# EasyEDAProProject.net
KiCad netlist of a schematic drawn in EasyEDA Pro
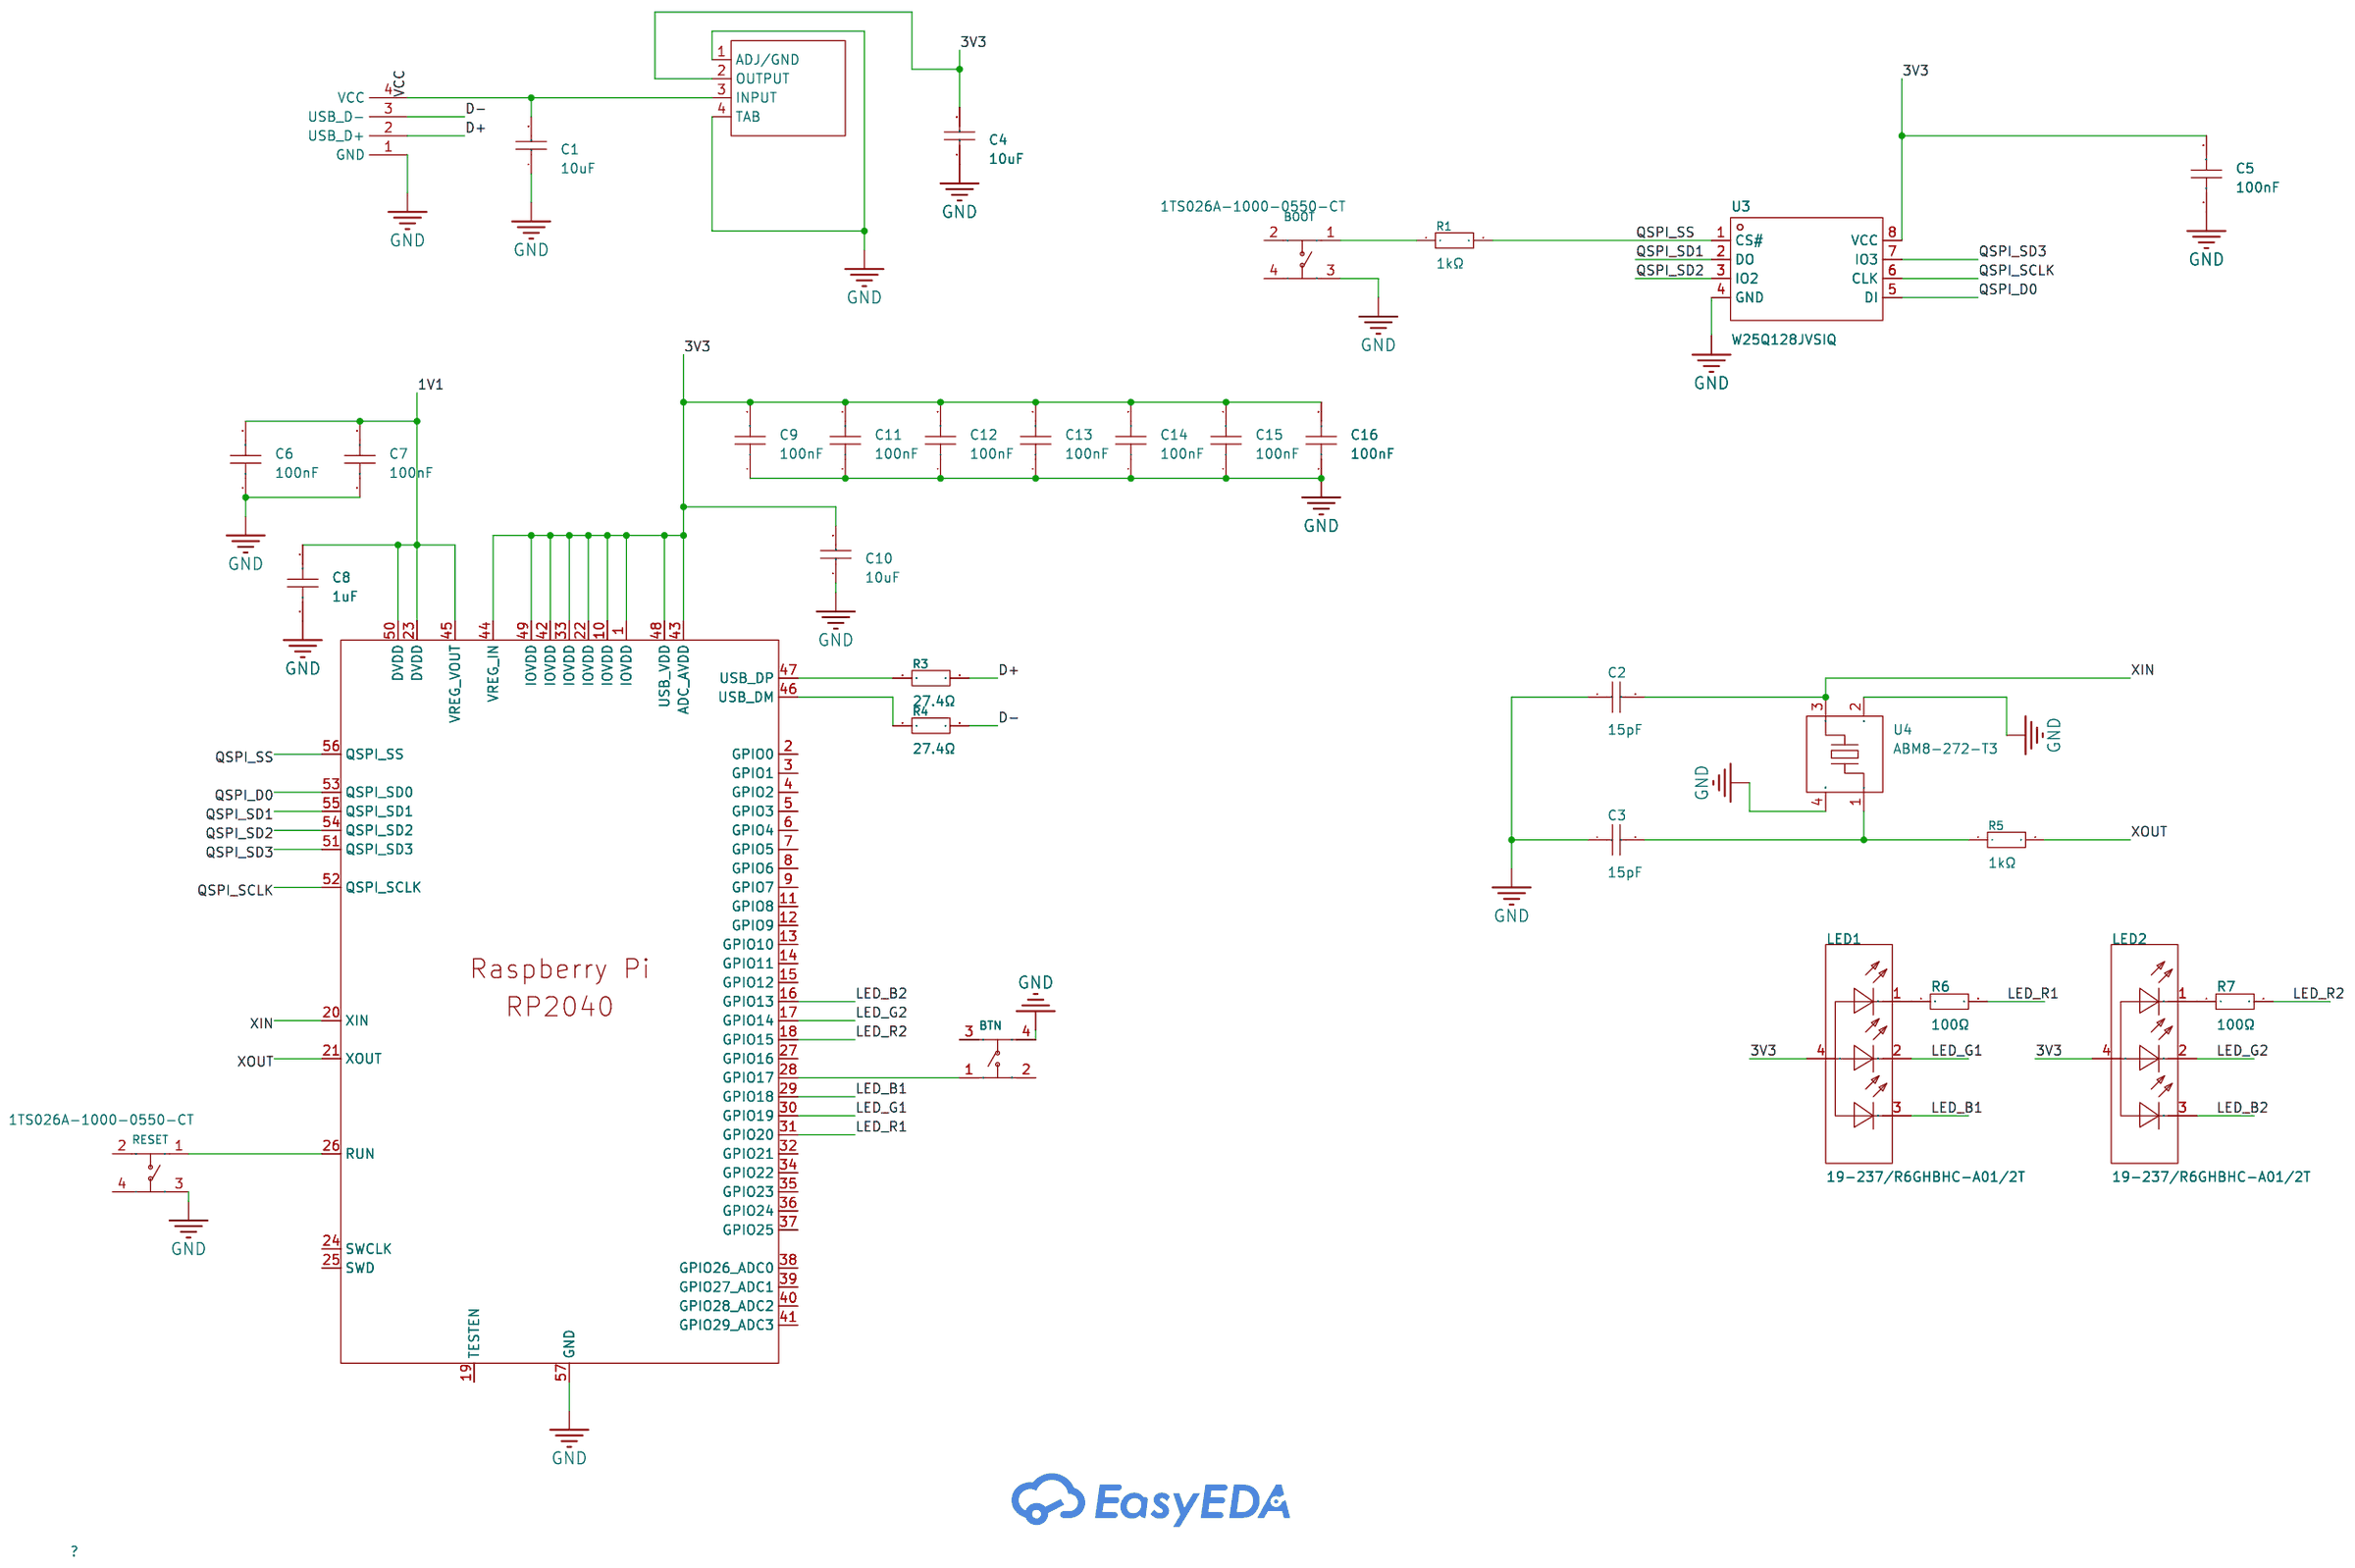
[diagram p0: schematic sheet]

(export (version "E")
  (design (tool "Eeschema 10.0.6"))
  (components
    (comp (ref "BOOT")
      (value "1TS026A-1000-0550-CT")
      (footprint "easyedapro:SW-SMD_4P-L2.6-W1.6-P0.75-LS3.0")
      (fields (field (name "Manufacturer") "HYP(鸿源精密)"))
      (libsource (lib "easyedapro") (part "1TS026A-1000-0550-CT"))
    )
    (comp (ref "BTN")
      (value "1TS026A-1000-0550-CT")
      (footprint "easyedapro:SW-SMD_4P-L2.6-W1.6-P0.75-LS3.0")
      (fields (field (name "Manufacturer") "HYP(鸿源精密)"))
      (libsource (lib "easyedapro") (part "1TS026A-1000-0550-CT"))
    )
    (comp (ref "C1")
      (value "10uF")
      (footprint "easyedapro:C0402")
      (fields
        (field (name "Manufacturer Part") "CL05A106MQ5NUNC")
        (field (name "Manufacturer") "SAMSUNG(三星)")
      )
      (libsource (lib "easyedapro") (part "CL05A106MQ5NUNC"))
    )
    (comp (ref "C2")
      (value "15pF")
      (footprint "easyedapro:C0402")
      (fields (field (name "Manufacturer Part") "0402CG150J500NT") (field (name "Manufacturer") "FH(风华)"))
      (libsource (lib "easyedapro") (part "0402CG150J500NT"))
    )
    (comp (ref "C3")
      (value "15pF")
      (footprint "easyedapro:C0402")
      (fields (field (name "Manufacturer Part") "0402CG150J500NT") (field (name "Manufacturer") "FH(风华)"))
      (libsource (lib "easyedapro") (part "0402CG150J500NT"))
    )
    (comp (ref "C4")
      (value "10uF")
      (footprint "easyedapro:C0402")
      (fields
        (field (name "Manufacturer Part") "CL05A106MQ5NUNC")
        (field (name "Manufacturer") "SAMSUNG(三星)")
      )
      (libsource (lib "easyedapro") (part "CL05A106MQ5NUNC"))
    )
    (comp (ref "C5")
      (value "100nF")
      (footprint "easyedapro:C0402")
      (fields
        (field (name "Manufacturer Part") "CL05B104KO5NNNC")
        (field (name "Manufacturer") "SAMSUNG(三星)")
      )
      (libsource (lib "easyedapro") (part "CL05B104KO5NNNC"))
    )
    (comp (ref "C6")
      (value "100nF")
      (footprint "easyedapro:C0402")
      (fields
        (field (name "Manufacturer Part") "CL05B104KO5NNNC")
        (field (name "Manufacturer") "SAMSUNG(三星)")
      )
      (libsource (lib "easyedapro") (part "CL05B104KO5NNNC"))
    )
    (comp (ref "C7")
      (value "100nF")
      (footprint "easyedapro:C0402")
      (fields
        (field (name "Manufacturer Part") "CL05B104KO5NNNC")
        (field (name "Manufacturer") "SAMSUNG(三星)")
      )
      (libsource (lib "easyedapro") (part "CL05B104KO5NNNC"))
    )
    (comp (ref "C8")
      (value "1uF")
      (footprint "easyedapro:C0402")
      (fields
        (field (name "Manufacturer Part") "CL05A105KA5NQNC")
        (field (name "Manufacturer") "SAMSUNG(三星)")
      )
      (libsource (lib "easyedapro") (part "CL05A105KA5NQNC"))
    )
    (comp (ref "C9")
      (value "100nF")
      (footprint "easyedapro:C0402")
      (fields
        (field (name "Manufacturer Part") "CL05B104KO5NNNC")
        (field (name "Manufacturer") "SAMSUNG(三星)")
      )
      (libsource (lib "easyedapro") (part "CL05B104KO5NNNC"))
    )
    (comp (ref "C10")
      (value "10uF")
      (footprint "easyedapro:C0402")
      (fields
        (field (name "Manufacturer Part") "CL05A106MQ5NUNC")
        (field (name "Manufacturer") "SAMSUNG(三星)")
      )
      (libsource (lib "easyedapro") (part "CL05A106MQ5NUNC"))
    )
    (comp (ref "C11")
      (value "100nF")
      (footprint "easyedapro:C0402")
      (fields
        (field (name "Manufacturer Part") "CL05B104KO5NNNC")
        (field (name "Manufacturer") "SAMSUNG(三星)")
      )
      (libsource (lib "easyedapro") (part "CL05B104KO5NNNC"))
    )
    (comp (ref "C12")
      (value "100nF")
      (footprint "easyedapro:C0402")
      (fields
        (field (name "Manufacturer Part") "CL05B104KO5NNNC")
        (field (name "Manufacturer") "SAMSUNG(三星)")
      )
      (libsource (lib "easyedapro") (part "CL05B104KO5NNNC"))
    )
    (comp (ref "C13")
      (value "100nF")
      (footprint "easyedapro:C0402")
      (fields
        (field (name "Manufacturer Part") "CL05B104KO5NNNC")
        (field (name "Manufacturer") "SAMSUNG(三星)")
      )
      (libsource (lib "easyedapro") (part "CL05B104KO5NNNC"))
    )
    (comp (ref "C14")
      (value "100nF")
      (footprint "easyedapro:C0402")
      (fields
        (field (name "Manufacturer Part") "CL05B104KO5NNNC")
        (field (name "Manufacturer") "SAMSUNG(三星)")
      )
      (libsource (lib "easyedapro") (part "CL05B104KO5NNNC"))
    )
    (comp (ref "C15")
      (value "100nF")
      (footprint "easyedapro:C0402")
      (fields
        (field (name "Manufacturer Part") "CL05B104KO5NNNC")
        (field (name "Manufacturer") "SAMSUNG(三星)")
      )
      (libsource (lib "easyedapro") (part "CL05B104KO5NNNC"))
    )
    (comp (ref "C16")
      (value "100nF")
      (footprint "easyedapro:C0402")
      (fields
        (field (name "Manufacturer Part") "CL05B104KO5NNNC")
        (field (name "Manufacturer") "SAMSUNG(三星)")
      )
      (libsource (lib "easyedapro") (part "CL05B104KO5NNNC"))
    )
    (comp (ref "LED1")
      (value "19-237/R6GHBHC-A01/2T")
      (footprint "easyedapro:LED-ARRAY-SMD_4P-L1.6-W1.6-BL-CW")
      (fields (field (name "Manufacturer") "EVERLIGHT(亿光)"))
      (libsource (lib "easyedapro") (part "19-237/R6GHBHC-A01/2T"))
    )
    (comp (ref "LED2")
      (value "19-237/R6GHBHC-A01/2T")
      (footprint "easyedapro:LED-ARRAY-SMD_4P-L1.6-W1.6-BL-CW")
      (fields (field (name "Manufacturer") "EVERLIGHT(亿光)"))
      (libsource (lib "easyedapro") (part "19-237/R6GHBHC-A01/2T"))
    )
    (comp (ref "R1")
      (value "1kΩ")
      (footprint "easyedapro:R0402")
      (fields
        (field (name "Manufacturer Part") "0402WGF1001TCE")
        (field (name "Manufacturer") "UNI-ROYAL(厚声)")
      )
      (libsource (lib "easyedapro") (part "0402WGF1001TCE"))
    )
    (comp (ref "R3")
      (value "27.4Ω")
      (footprint "easyedapro:R0402")
      (fields
        (field (name "Manufacturer Part") "0402WGF274JTCE")
        (field (name "Manufacturer") "UNI-ROYAL(厚声)")
      )
      (libsource (lib "easyedapro") (part "0402WGF274JTCE"))
    )
    (comp (ref "R4")
      (value "27.4Ω")
      (footprint "easyedapro:R0402")
      (fields
        (field (name "Manufacturer Part") "0402WGF274JTCE")
        (field (name "Manufacturer") "UNI-ROYAL(厚声)")
      )
      (libsource (lib "easyedapro") (part "0402WGF274JTCE"))
    )
    (comp (ref "R5")
      (value "1kΩ")
      (footprint "easyedapro:R0402")
      (fields
        (field (name "Manufacturer Part") "0402WGF1001TCE")
        (field (name "Manufacturer") "UNI-ROYAL(厚声)")
      )
      (libsource (lib "easyedapro") (part "0402WGF1001TCE"))
    )
    (comp (ref "R6")
      (value "100Ω")
      (footprint "easyedapro:R0402")
      (fields
        (field (name "Manufacturer Part") "0402WGF1000TCE")
        (field (name "Manufacturer") "UNI-ROYAL(厚声)")
      )
      (libsource (lib "easyedapro") (part "0402WGF1000TCE"))
    )
    (comp (ref "R7")
      (value "100Ω")
      (footprint "easyedapro:R0402")
      (fields
        (field (name "Manufacturer Part") "0402WGF1000TCE")
        (field (name "Manufacturer") "UNI-ROYAL(厚声)")
      )
      (libsource (lib "easyedapro") (part "0402WGF1000TCE"))
    )
    (comp (ref "RESET")
      (value "1TS026A-1000-0550-CT")
      (footprint "easyedapro:SW-SMD_4P-L2.6-W1.6-P0.75-LS3.0")
      (fields (field (name "Manufacturer") "HYP(鸿源精密)"))
      (libsource (lib "easyedapro") (part "1TS026A-1000-0550-CT"))
    )
    (comp (ref "U1")
      (value "RP2040")
      (footprint "easyedapro:QFN-56_L7.0-W7.0-P0.40-TL-EP4.0")
      (fields (field (name "Manufacturer") "Raspberry Pi(树莓派)"))
      (libsource (lib "easyedapro") (part "RP2040_C2961140"))
    )
    (comp (ref "U2")
      (value "NCP1117ST33T3G")
      (footprint "easyedapro:SOT-223-3_L6.5-W3.4-P2.30-LS7.0-BR")
      (fields (field (name "Manufacturer") "onsemi(安森美)"))
      (libsource (lib "easyedapro") (part "NCP1117ST33T3G"))
    )
    (comp (ref "U3")
      (value "W25Q128JVSIQ")
      (footprint "easyedapro:SOIC-8_L5.3-W5.3-P1.27-LS8.0-BL")
      (fields (field (name "Manufacturer") "WINBOND(华邦)"))
      (libsource (lib "easyedapro") (part "W25Q128JVSIQTR"))
    )
    (comp (ref "U4")
      (value "ABM8-272-T3")
      (footprint "easyedapro:CRYSTAL-SMD_4P-L3.2-W2.5-BL")
      (fields (field (name "Manufacturer") "ABRACON"))
      (libsource (lib "easyedapro") (part "ABM8-272-T3_C20625731"))
    )
    (comp (ref "X1")
      (value "~")
      (footprint "easyedapro:USBA_PCB")
      (description "USB-A PCB")
      (libsource (lib "easyedapro") (part "USBA_PCB"))
    )
  )
  (nets
    (net (code "1") (name "/1V1") (class "Default")
      (node (ref "C6") (pin "2") (pinfunction "2_2") (pintype "unspecified"))
      (node (ref "C7") (pin "2") (pinfunction "2_2") (pintype "unspecified"))
      (node (ref "C8") (pin "2") (pinfunction "2_2") (pintype "unspecified"))
      (node (ref "U1") (pin "23") (pinfunction "DVDD_23") (pintype "bidirectional"))
      (node (ref "U1") (pin "45") (pinfunction "VREG_VOUT_45") (pintype "bidirectional"))
      (node (ref "U1") (pin "50") (pinfunction "DVDD_50") (pintype "bidirectional"))
    )
    (net (code "2") (name "/3V3") (class "Default")
      (node (ref "C10") (pin "2") (pinfunction "2_2") (pintype "input"))
      (node (ref "C11") (pin "2") (pinfunction "2_2") (pintype "unspecified"))
      (node (ref "C12") (pin "2") (pinfunction "2_2") (pintype "unspecified"))
      (node (ref "C13") (pin "2") (pinfunction "2_2") (pintype "unspecified"))
      (node (ref "C14") (pin "2") (pinfunction "2_2") (pintype "unspecified"))
      (node (ref "C15") (pin "2") (pinfunction "2_2") (pintype "unspecified"))
      (node (ref "C16") (pin "2") (pinfunction "2_2") (pintype "unspecified"))
      (node (ref "C4") (pin "2") (pinfunction "2_2") (pintype "input"))
      (node (ref "C5") (pin "2") (pinfunction "2_2") (pintype "unspecified"))
      (node (ref "C9") (pin "2") (pinfunction "2_2") (pintype "unspecified"))
      (node (ref "LED1") (pin "4") (pinfunction "+_4") (pintype "unspecified"))
      (node (ref "LED2") (pin "4") (pinfunction "+_4") (pintype "unspecified"))
      (node (ref "U1") (pin "1") (pinfunction "IOVDD_1") (pintype "bidirectional"))
      (node (ref "U1") (pin "10") (pinfunction "IOVDD_10") (pintype "bidirectional"))
      (node (ref "U1") (pin "22") (pinfunction "IOVDD_22") (pintype "bidirectional"))
      (node (ref "U1") (pin "33") (pinfunction "IOVDD_33") (pintype "bidirectional"))
      (node (ref "U1") (pin "42") (pinfunction "IOVDD_42") (pintype "bidirectional"))
      (node (ref "U1") (pin "43") (pinfunction "ADC_AVDD_43") (pintype "bidirectional"))
      (node (ref "U1") (pin "44") (pinfunction "VREG_IN_44") (pintype "bidirectional"))
      (node (ref "U1") (pin "48") (pinfunction "USB_VDD_48") (pintype "bidirectional"))
      (node (ref "U1") (pin "49") (pinfunction "IOVDD_49") (pintype "bidirectional"))
      (node (ref "U2") (pin "2") (pinfunction "OUTPUT_2") (pintype "unspecified"))
      (node (ref "U3") (pin "8") (pinfunction "VCC_8") (pintype "unspecified"))
    )
    (net (code "3") (name "/D+") (class "Default")
      (node (ref "R3") (pin "2") (pinfunction "2_2") (pintype "input"))
      (node (ref "X1") (pin "2") (pinfunction "USB_D+_2") (pintype "input"))
    )
    (net (code "4") (name "/D-") (class "Default")
      (node (ref "R4") (pin "2") (pinfunction "2_2") (pintype "input"))
      (node (ref "X1") (pin "3") (pinfunction "USB_D-_3") (pintype "input"))
    )
    (net (code "5") (name "/LED_B1") (class "Default")
      (node (ref "LED1") (pin "3") (pinfunction "B-_3") (pintype "unspecified"))
      (node (ref "U1") (pin "29") (pinfunction "GPIO18_29") (pintype "bidirectional"))
    )
    (net (code "6") (name "/LED_B2") (class "Default")
      (node (ref "LED2") (pin "3") (pinfunction "B-_3") (pintype "unspecified"))
      (node (ref "U1") (pin "16") (pinfunction "GPIO13_16") (pintype "bidirectional"))
    )
    (net (code "7") (name "/LED_G1") (class "Default")
      (node (ref "LED1") (pin "2") (pinfunction "G-_2") (pintype "unspecified"))
      (node (ref "U1") (pin "30") (pinfunction "GPIO19_30") (pintype "bidirectional"))
    )
    (net (code "8") (name "/LED_G2") (class "Default")
      (node (ref "LED2") (pin "2") (pinfunction "G-_2") (pintype "unspecified"))
      (node (ref "U1") (pin "17") (pinfunction "GPIO14_17") (pintype "bidirectional"))
    )
    (net (code "9") (name "/LED_R1") (class "Default")
      (node (ref "R6") (pin "2") (pinfunction "2_2") (pintype "input"))
      (node (ref "U1") (pin "31") (pinfunction "GPIO20_31") (pintype "bidirectional"))
    )
    (net (code "10") (name "/LED_R2") (class "Default")
      (node (ref "R7") (pin "2") (pinfunction "2_2") (pintype "input"))
      (node (ref "U1") (pin "18") (pinfunction "GPIO15_18") (pintype "bidirectional"))
    )
    (net (code "11") (name "/QSPI_D0") (class "Default")
      (node (ref "U1") (pin "53") (pinfunction "QSPI_SD0_53") (pintype "bidirectional"))
      (node (ref "U3") (pin "5") (pinfunction "DI_5") (pintype "unspecified"))
    )
    (net (code "12") (name "/QSPI_SCLK") (class "Default")
      (node (ref "U1") (pin "52") (pinfunction "QSPI_SCLK_52") (pintype "output"))
      (node (ref "U3") (pin "6") (pinfunction "CLK_6") (pintype "unspecified"))
    )
    (net (code "13") (name "/QSPI_SD1") (class "Default")
      (node (ref "U1") (pin "55") (pinfunction "QSPI_SD1_55") (pintype "bidirectional"))
      (node (ref "U3") (pin "2") (pinfunction "DO_2") (pintype "unspecified"))
    )
    (net (code "14") (name "/QSPI_SD2") (class "Default")
      (node (ref "U1") (pin "54") (pinfunction "QSPI_SD2_54") (pintype "bidirectional"))
      (node (ref "U3") (pin "3") (pinfunction "IO2_3") (pintype "unspecified"))
    )
    (net (code "15") (name "/QSPI_SD3") (class "Default")
      (node (ref "U1") (pin "51") (pinfunction "QSPI_SD3_51") (pintype "bidirectional"))
      (node (ref "U3") (pin "7") (pinfunction "IO3_7") (pintype "unspecified"))
    )
    (net (code "16") (name "/QSPI_SS") (class "Default")
      (node (ref "R1") (pin "2") (pinfunction "2_2") (pintype "input"))
      (node (ref "U1") (pin "56") (pinfunction "QSPI_SS_56") (pintype "bidirectional"))
      (node (ref "U3") (pin "1") (pinfunction "CS#_1") (pintype "unspecified"))
    )
    (net (code "17") (name "/VCC") (class "Default")
      (node (ref "C1") (pin "2") (pinfunction "2_2") (pintype "input"))
      (node (ref "U2") (pin "3") (pinfunction "INPUT_3") (pintype "unspecified"))
      (node (ref "X1") (pin "4") (pinfunction "VCC_4") (pintype "input"))
    )
    (net (code "18") (name "/XIN") (class "Default")
      (node (ref "C2") (pin "2") (pinfunction "2_2") (pintype "input"))
      (node (ref "U1") (pin "20") (pinfunction "XIN_20") (pintype "input"))
      (node (ref "U4") (pin "3") (pinfunction "3_3") (pintype "input"))
    )
    (net (code "19") (name "/XOUT") (class "Default")
      (node (ref "R5") (pin "2") (pinfunction "2_2") (pintype "input"))
      (node (ref "U1") (pin "21") (pinfunction "XOUT_21") (pintype "unspecified"))
    )
    (net (code "20") (name "GND") (class "Default")
      (node (ref "BOOT") (pin "3") (pinfunction "3_3") (pintype "input"))
      (node (ref "BTN") (pin "4") (pinfunction "4_4") (pintype "input"))
      (node (ref "C1") (pin "1") (pinfunction "1_1") (pintype "input"))
      (node (ref "C10") (pin "1") (pinfunction "1_1") (pintype "input"))
      (node (ref "C11") (pin "1") (pinfunction "1_1") (pintype "unspecified"))
      (node (ref "C12") (pin "1") (pinfunction "1_1") (pintype "unspecified"))
      (node (ref "C13") (pin "1") (pinfunction "1_1") (pintype "unspecified"))
      (node (ref "C14") (pin "1") (pinfunction "1_1") (pintype "unspecified"))
      (node (ref "C15") (pin "1") (pinfunction "1_1") (pintype "unspecified"))
      (node (ref "C16") (pin "1") (pinfunction "1_1") (pintype "unspecified"))
      (node (ref "C2") (pin "1") (pinfunction "1_1") (pintype "input"))
      (node (ref "C3") (pin "1") (pinfunction "1_1") (pintype "input"))
      (node (ref "C4") (pin "1") (pinfunction "1_1") (pintype "input"))
      (node (ref "C5") (pin "1") (pinfunction "1_1") (pintype "unspecified"))
      (node (ref "C6") (pin "1") (pinfunction "1_1") (pintype "unspecified"))
      (node (ref "C7") (pin "1") (pinfunction "1_1") (pintype "unspecified"))
      (node (ref "C8") (pin "1") (pinfunction "1_1") (pintype "unspecified"))
      (node (ref "C9") (pin "1") (pinfunction "1_1") (pintype "unspecified"))
      (node (ref "RESET") (pin "3") (pinfunction "3_3") (pintype "input"))
      (node (ref "U1") (pin "57") (pinfunction "GND_57") (pintype "bidirectional"))
      (node (ref "U2") (pin "1") (pinfunction "ADJ/GND_1") (pintype "unspecified"))
      (node (ref "U2") (pin "4") (pinfunction "TAB_4") (pintype "unspecified"))
      (node (ref "U3") (pin "4") (pinfunction "GND_4") (pintype "unspecified"))
      (node (ref "U4") (pin "2") (pinfunction "GND_2") (pintype "input"))
      (node (ref "U4") (pin "4") (pinfunction "GND_4") (pintype "input"))
      (node (ref "X1") (pin "1") (pinfunction "GND_1") (pintype "input"))
    )
    (net (code "21") (name "Net-(BOOT-Pad1)") (class "Default")
      (node (ref "BOOT") (pin "1") (pinfunction "1_1") (pintype "input"))
      (node (ref "R1") (pin "1") (pinfunction "1_1") (pintype "input"))
    )
    (net (code "22") (name "Net-(C3-Pad2)") (class "Default")
      (node (ref "C3") (pin "2") (pinfunction "2_2") (pintype "input"))
      (node (ref "R5") (pin "1") (pinfunction "1_1") (pintype "input"))
      (node (ref "U4") (pin "1") (pinfunction "1_1") (pintype "input"))
    )
    (net (code "23") (name "Net-(LED1-R-)") (class "Default")
      (node (ref "LED1") (pin "1") (pinfunction "R-_1") (pintype "unspecified"))
      (node (ref "R6") (pin "1") (pinfunction "1_1") (pintype "input"))
    )
    (net (code "24") (name "Net-(LED2-R-)") (class "Default")
      (node (ref "LED2") (pin "1") (pinfunction "R-_1") (pintype "unspecified"))
      (node (ref "R7") (pin "1") (pinfunction "1_1") (pintype "input"))
    )
    (net (code "25") (name "Net-(U1-GPIO17)") (class "Default")
      (node (ref "BTN") (pin "1") (pinfunction "1_1") (pintype "input"))
      (node (ref "U1") (pin "28") (pinfunction "GPIO17_28") (pintype "bidirectional"))
    )
    (net (code "26") (name "Net-(U1-RUN)") (class "Default")
      (node (ref "RESET") (pin "1") (pinfunction "1_1") (pintype "input"))
      (node (ref "U1") (pin "26") (pinfunction "RUN_26") (pintype "input"))
    )
    (net (code "27") (name "Net-(U1-USB_DM)") (class "Default")
      (node (ref "R4") (pin "1") (pinfunction "1_1") (pintype "input"))
      (node (ref "U1") (pin "46") (pinfunction "USB_DM_46") (pintype "bidirectional"))
    )
    (net (code "28") (name "Net-(U1-USB_DP)") (class "Default")
      (node (ref "R3") (pin "1") (pinfunction "1_1") (pintype "input"))
      (node (ref "U1") (pin "47") (pinfunction "USB_DP_47") (pintype "bidirectional"))
    )
    (net (code "29") (name "unconnected-(BOOT-Pad2)") (class "Default")
      (node (ref "BOOT") (pin "2") (pinfunction "2_2") (pintype "input"))
    )
    (net (code "30") (name "unconnected-(BOOT-Pad4)") (class "Default")
      (node (ref "BOOT") (pin "4") (pinfunction "4_4") (pintype "input"))
    )
    (net (code "31") (name "unconnected-(BTN-Pad2)") (class "Default")
      (node (ref "BTN") (pin "2") (pinfunction "2_2") (pintype "input"))
    )
    (net (code "32") (name "unconnected-(BTN-Pad3)") (class "Default")
      (node (ref "BTN") (pin "3") (pinfunction "3_3") (pintype "input"))
    )
    (net (code "33") (name "unconnected-(RESET-Pad2)") (class "Default")
      (node (ref "RESET") (pin "2") (pinfunction "2_2") (pintype "input"))
    )
    (net (code "34") (name "unconnected-(RESET-Pad4)") (class "Default")
      (node (ref "RESET") (pin "4") (pinfunction "4_4") (pintype "input"))
    )
    (net (code "35") (name "unconnected-(U1-GPIO0-Pad2)") (class "Default")
      (node (ref "U1") (pin "2") (pinfunction "GPIO0_2") (pintype "bidirectional"))
    )
    (net (code "36") (name "unconnected-(U1-GPIO1-Pad3)") (class "Default")
      (node (ref "U1") (pin "3") (pinfunction "GPIO1_3") (pintype "bidirectional"))
    )
    (net (code "37") (name "unconnected-(U1-GPIO2-Pad4)") (class "Default")
      (node (ref "U1") (pin "4") (pinfunction "GPIO2_4") (pintype "bidirectional"))
    )
    (net (code "38") (name "unconnected-(U1-GPIO3-Pad5)") (class "Default")
      (node (ref "U1") (pin "5") (pinfunction "GPIO3_5") (pintype "bidirectional"))
    )
    (net (code "39") (name "unconnected-(U1-GPIO4-Pad6)") (class "Default")
      (node (ref "U1") (pin "6") (pinfunction "GPIO4_6") (pintype "bidirectional"))
    )
    (net (code "40") (name "unconnected-(U1-GPIO5-Pad7)") (class "Default")
      (node (ref "U1") (pin "7") (pinfunction "GPIO5_7") (pintype "bidirectional"))
    )
    (net (code "41") (name "unconnected-(U1-GPIO6-Pad8)") (class "Default")
      (node (ref "U1") (pin "8") (pinfunction "GPIO6_8") (pintype "bidirectional"))
    )
    (net (code "42") (name "unconnected-(U1-GPIO7-Pad9)") (class "Default")
      (node (ref "U1") (pin "9") (pinfunction "GPIO7_9") (pintype "bidirectional"))
    )
    (net (code "43") (name "unconnected-(U1-GPIO8-Pad11)") (class "Default")
      (node (ref "U1") (pin "11") (pinfunction "GPIO8_11") (pintype "bidirectional"))
    )
    (net (code "44") (name "unconnected-(U1-GPIO9-Pad12)") (class "Default")
      (node (ref "U1") (pin "12") (pinfunction "GPIO9_12") (pintype "bidirectional"))
    )
    (net (code "45") (name "unconnected-(U1-GPIO10-Pad13)") (class "Default")
      (node (ref "U1") (pin "13") (pinfunction "GPIO10_13") (pintype "bidirectional"))
    )
    (net (code "46") (name "unconnected-(U1-GPIO11-Pad14)") (class "Default")
      (node (ref "U1") (pin "14") (pinfunction "GPIO11_14") (pintype "bidirectional"))
    )
    (net (code "47") (name "unconnected-(U1-GPIO12-Pad15)") (class "Default")
      (node (ref "U1") (pin "15") (pinfunction "GPIO12_15") (pintype "bidirectional"))
    )
    (net (code "48") (name "unconnected-(U1-GPIO16-Pad27)") (class "Default")
      (node (ref "U1") (pin "27") (pinfunction "GPIO16_27") (pintype "bidirectional"))
    )
    (net (code "49") (name "unconnected-(U1-GPIO21-Pad32)") (class "Default")
      (node (ref "U1") (pin "32") (pinfunction "GPIO21_32") (pintype "bidirectional"))
    )
    (net (code "50") (name "unconnected-(U1-GPIO22-Pad34)") (class "Default")
      (node (ref "U1") (pin "34") (pinfunction "GPIO22_34") (pintype "bidirectional"))
    )
    (net (code "51") (name "unconnected-(U1-GPIO23-Pad35)") (class "Default")
      (node (ref "U1") (pin "35") (pinfunction "GPIO23_35") (pintype "bidirectional"))
    )
    (net (code "52") (name "unconnected-(U1-GPIO24-Pad36)") (class "Default")
      (node (ref "U1") (pin "36") (pinfunction "GPIO24_36") (pintype "bidirectional"))
    )
    (net (code "53") (name "unconnected-(U1-GPIO25-Pad37)") (class "Default")
      (node (ref "U1") (pin "37") (pinfunction "GPIO25_37") (pintype "bidirectional"))
    )
    (net (code "54") (name "unconnected-(U1-GPIO26_ADC0-Pad38)") (class "Default")
      (node (ref "U1") (pin "38") (pinfunction "GPIO26_ADC0_38") (pintype "bidirectional"))
    )
    (net (code "55") (name "unconnected-(U1-GPIO27_ADC1-Pad39)") (class "Default")
      (node (ref "U1") (pin "39") (pinfunction "GPIO27_ADC1_39") (pintype "bidirectional"))
    )
    (net (code "56") (name "unconnected-(U1-GPIO28_ADC2-Pad40)") (class "Default")
      (node (ref "U1") (pin "40") (pinfunction "GPIO28_ADC2_40") (pintype "bidirectional"))
    )
    (net (code "57") (name "unconnected-(U1-GPIO29_ADC3-Pad41)") (class "Default")
      (node (ref "U1") (pin "41") (pinfunction "GPIO29_ADC3_41") (pintype "bidirectional"))
    )
    (net (code "58") (name "unconnected-(U1-SWCLK-Pad24)") (class "Default")
      (node (ref "U1") (pin "24") (pinfunction "SWCLK_24") (pintype "output"))
    )
    (net (code "59") (name "unconnected-(U1-SWD-Pad25)") (class "Default")
      (node (ref "U1") (pin "25") (pinfunction "SWD_25") (pintype "bidirectional"))
    )
    (net (code "60") (name "unconnected-(U1-TESTEN-Pad19)") (class "Default")
      (node (ref "U1") (pin "19") (pinfunction "TESTEN_19") (pintype "unspecified"))
    )
  )
)
